# 7segDisplay.net
KiCad netlist of a schematic drawn in EAGLE
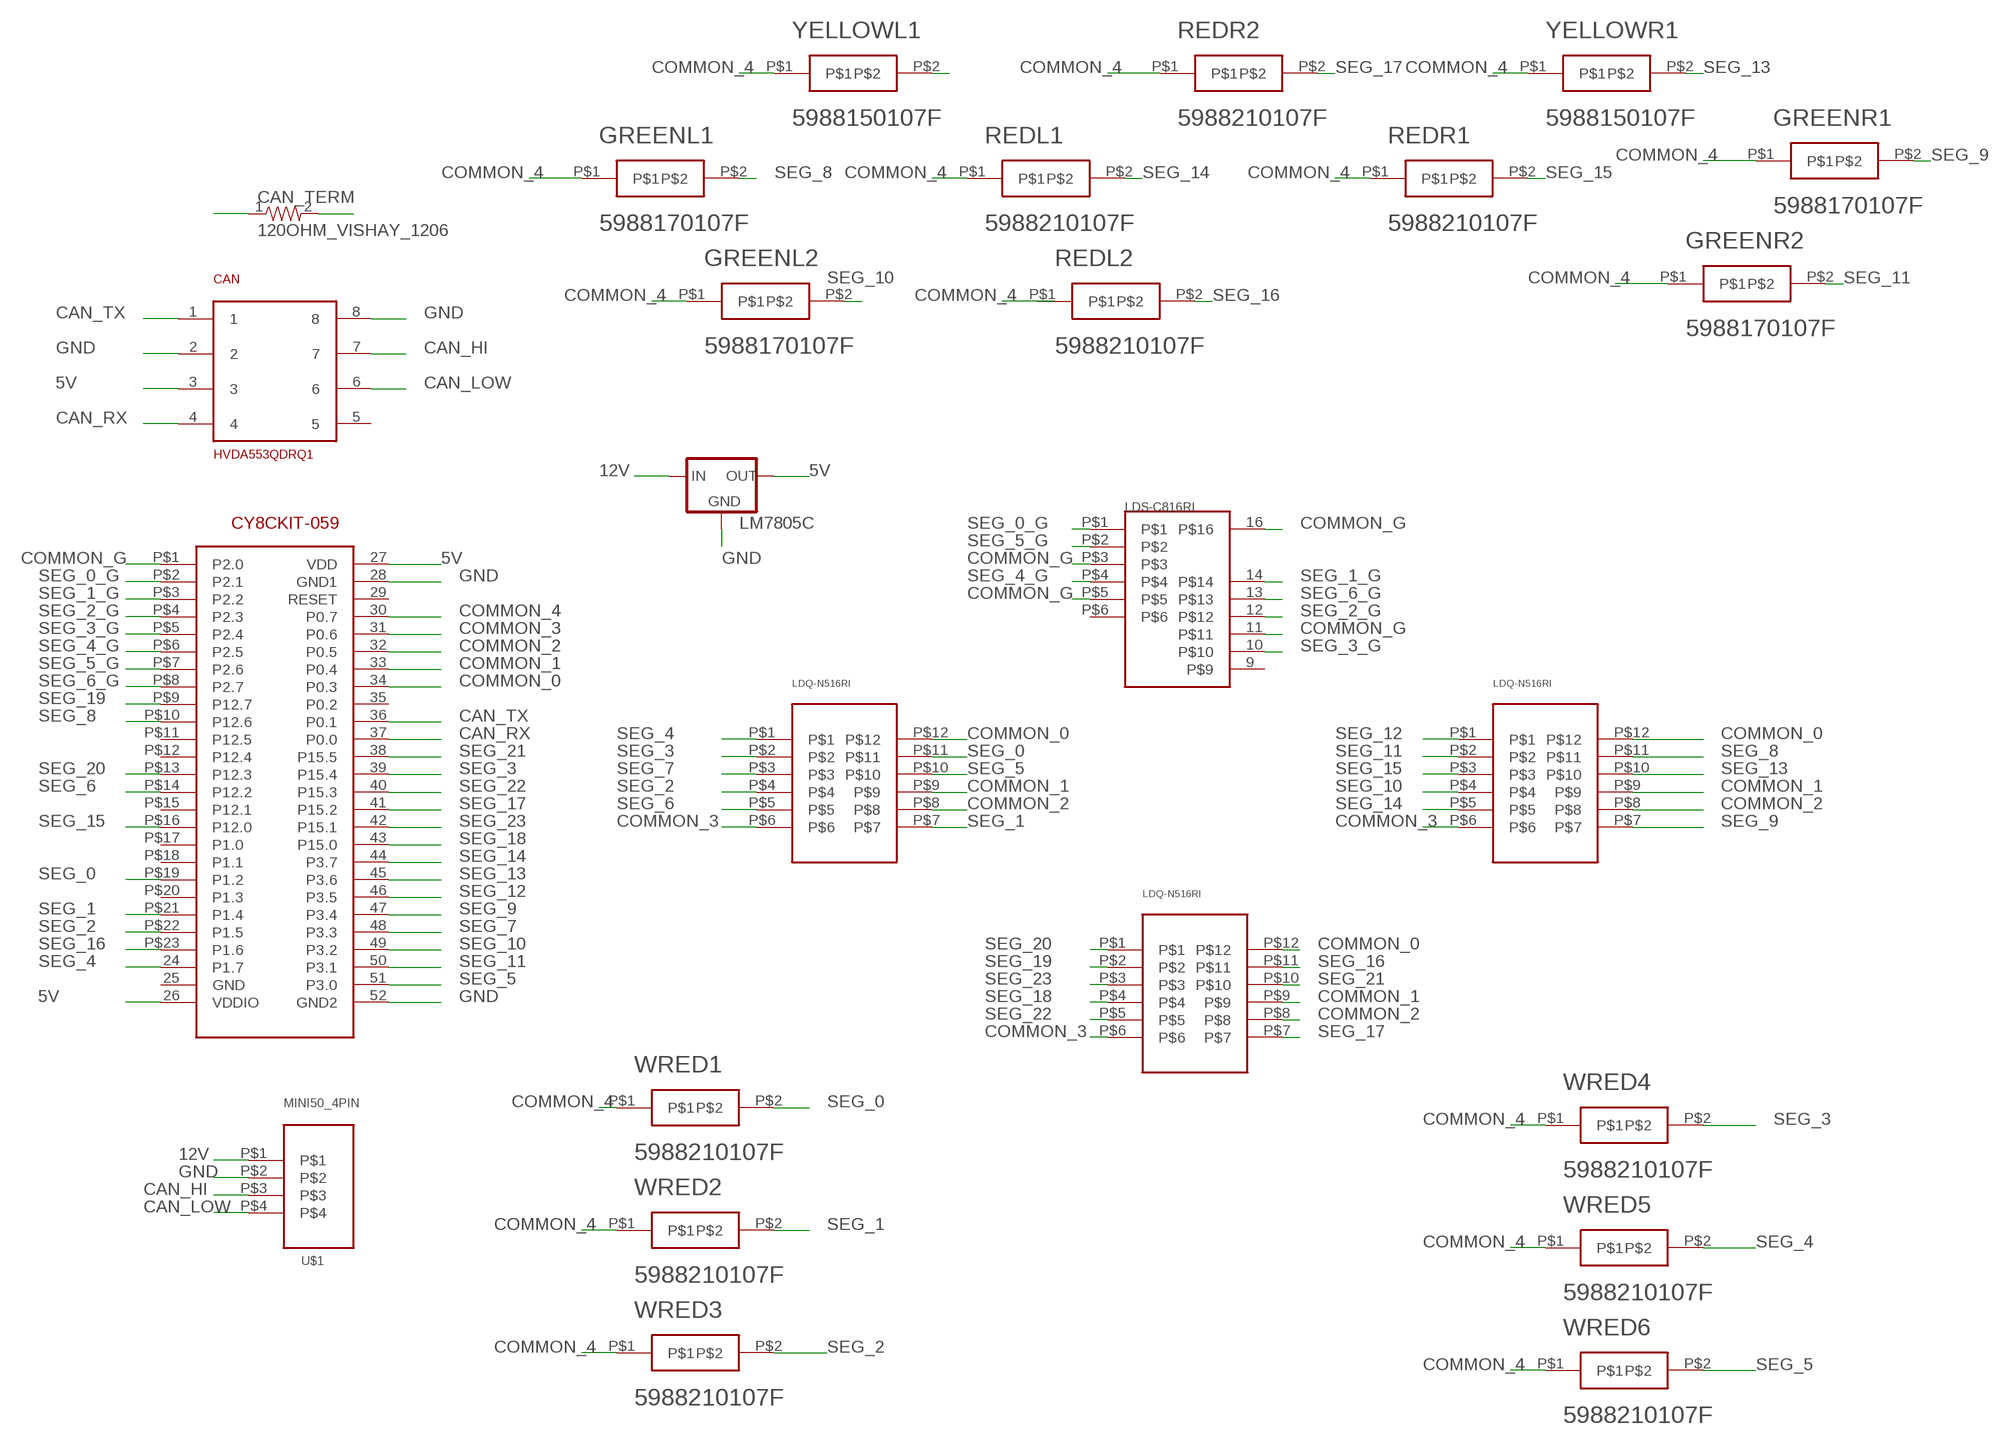
[diagram p0: schematic, sheet 1]

(export (version "E")
  (design (tool "Eeschema 10.0.6"))
  (components
    (comp (ref "BOTTOM")
      (value "LDQ-N516RI")
      (footprint "eagle-import:LDQ-N516RI")
      (libsource (lib "eagle-import") (part "LDQ-N516RI"))
    )
    (comp (ref "CAN")
      (value "HVDA553QDRQ1")
      (footprint "eagle-import:SOIC127P600X172-8N")
      (libsource (lib "eagle-import") (part "HVDA553QDRQ1"))
    )
    (comp (ref "CAN_TERM")
      (value "120OHM_VISHAY_1206")
      (footprint "eagle-import:1206")
      (libsource (lib "eagle-import") (part "120OHM_VISHAY_1206"))
    )
    (comp (ref "GEAR")
      (value "LDS-C816RITHROUGH_HOLE")
      (footprint "eagle-import:LDS-C816RI")
      (libsource (lib "eagle-import") (part "LDS-C816RITHROUGH_HOLE"))
    )
    (comp (ref "GREENL1")
      (value "5988170107F")
      (footprint "eagle-import:0805")
      (libsource (lib "eagle-import") (part "5988170107F"))
    )
    (comp (ref "GREENL2")
      (value "5988170107F")
      (footprint "eagle-import:0805")
      (libsource (lib "eagle-import") (part "5988170107F"))
    )
    (comp (ref "GREENR1")
      (value "5988170107F")
      (footprint "eagle-import:0805")
      (libsource (lib "eagle-import") (part "5988170107F"))
    )
    (comp (ref "GREENR2")
      (value "5988170107F")
      (footprint "eagle-import:0805")
      (libsource (lib "eagle-import") (part "5988170107F"))
    )
    (comp (ref "LEFT")
      (value "LDQ-N516RI")
      (footprint "eagle-import:LDQ-N516RI")
      (libsource (lib "eagle-import") (part "LDQ-N516RI"))
    )
    (comp (ref "LM7805C")
      (value "78XXL")
      (footprint "eagle-import:78XXL")
      (libsource (lib "eagle-import") (part "78XXL"))
    )
    (comp (ref "REDL1")
      (value "5988210107F")
      (footprint "eagle-import:1206")
      (libsource (lib "eagle-import") (part "5988210107F"))
    )
    (comp (ref "REDL2")
      (value "5988210107F")
      (footprint "eagle-import:1206")
      (libsource (lib "eagle-import") (part "5988210107F"))
    )
    (comp (ref "REDR1")
      (value "5988210107F")
      (footprint "eagle-import:1206")
      (libsource (lib "eagle-import") (part "5988210107F"))
    )
    (comp (ref "REDR2")
      (value "5988210107F")
      (footprint "eagle-import:1206")
      (libsource (lib "eagle-import") (part "5988210107F"))
    )
    (comp (ref "RIGHT")
      (value "LDQ-N516RI")
      (footprint "eagle-import:LDQ-N516RI")
      (libsource (lib "eagle-import") (part "LDQ-N516RI"))
    )
    (comp (ref "U$1")
      (value "MINI50_4PIN")
      (footprint "eagle-import:34792-0041")
      (libsource (lib "eagle-import") (part "MINI50_4PIN"))
    )
    (comp (ref "U$3")
      (value "CY8CKIT-059")
      (footprint "eagle-import:CY8CKIT-059")
      (libsource (lib "eagle-import") (part "CY8CKIT-059"))
    )
    (comp (ref "WRED1")
      (value "5988210107F")
      (footprint "eagle-import:1206")
      (libsource (lib "eagle-import") (part "5988210107F"))
    )
    (comp (ref "WRED2")
      (value "5988210107F")
      (footprint "eagle-import:1206")
      (libsource (lib "eagle-import") (part "5988210107F"))
    )
    (comp (ref "WRED3")
      (value "5988210107F")
      (footprint "eagle-import:1206")
      (libsource (lib "eagle-import") (part "5988210107F"))
    )
    (comp (ref "WRED4")
      (value "5988210107F")
      (footprint "eagle-import:1206")
      (libsource (lib "eagle-import") (part "5988210107F"))
    )
    (comp (ref "WRED5")
      (value "5988210107F")
      (footprint "eagle-import:1206")
      (libsource (lib "eagle-import") (part "5988210107F"))
    )
    (comp (ref "WRED6")
      (value "5988210107F")
      (footprint "eagle-import:1206")
      (libsource (lib "eagle-import") (part "5988210107F"))
    )
    (comp (ref "YELLOWL1")
      (value "5988150107F")
      (footprint "eagle-import:0805")
      (libsource (lib "eagle-import") (part "5988150107F"))
    )
    (comp (ref "YELLOWR1")
      (value "5988150107F")
      (footprint "eagle-import:0805")
      (libsource (lib "eagle-import") (part "5988150107F"))
    )
  )
  (nets
    (net (code "1") (name "/5V") (class "Default")
      (node (ref "CAN") (pin "3") (pinfunction "3_3") (pintype "bidirectional"))
      (node (ref "LM7805C") (pin "OUT") (pinfunction "OUT_OUT") (pintype "passive"))
      (node (ref "U$3") (pin "26") (pinfunction "VDDIO_26") (pintype "power_in"))
      (node (ref "U$3") (pin "27") (pinfunction "VDD_27") (pintype "power_in"))
    )
    (net (code "2") (name "/12V") (class "Default")
      (node (ref "LM7805C") (pin "IN") (pinfunction "IN_IN") (pintype "input"))
      (node (ref "U$1") (pin "P$1") (pinfunction "P$1_P$1") (pintype "bidirectional"))
    )
    (net (code "3") (name "/CAN_HI") (class "Default")
      (node (ref "CAN") (pin "7") (pinfunction "7_7") (pintype "bidirectional"))
      (node (ref "CAN_TERM") (pin "1") (pinfunction "1_1") (pintype "passive"))
      (node (ref "U$1") (pin "P$3") (pinfunction "P$3_P$3") (pintype "bidirectional"))
    )
    (net (code "4") (name "/CAN_LOW") (class "Default")
      (node (ref "CAN") (pin "6") (pinfunction "6_6") (pintype "bidirectional"))
      (node (ref "CAN_TERM") (pin "2") (pinfunction "2_2") (pintype "passive"))
      (node (ref "U$1") (pin "P$4") (pinfunction "P$4_P$4") (pintype "bidirectional"))
    )
    (net (code "5") (name "/CAN_RX") (class "Default")
      (node (ref "CAN") (pin "4") (pinfunction "4_4") (pintype "bidirectional"))
      (node (ref "U$3") (pin "37") (pinfunction "P0.0_37") (pintype "bidirectional"))
    )
    (net (code "6") (name "/CAN_TX") (class "Default")
      (node (ref "CAN") (pin "1") (pinfunction "1_1") (pintype "bidirectional"))
      (node (ref "U$3") (pin "36") (pinfunction "P0.1_36") (pintype "bidirectional"))
    )
    (net (code "7") (name "/COMMON_0") (class "Default")
      (node (ref "BOTTOM") (pin "P$12") (pinfunction "P$12_P$12") (pintype "bidirectional"))
      (node (ref "LEFT") (pin "P$12") (pinfunction "P$12_P$12") (pintype "bidirectional"))
      (node (ref "RIGHT") (pin "P$12") (pinfunction "P$12_P$12") (pintype "bidirectional"))
      (node (ref "U$3") (pin "34") (pinfunction "P0.3_34") (pintype "bidirectional"))
    )
    (net (code "8") (name "/COMMON_1") (class "Default")
      (node (ref "BOTTOM") (pin "P$9") (pinfunction "P$9_P$9") (pintype "bidirectional"))
      (node (ref "LEFT") (pin "P$9") (pinfunction "P$9_P$9") (pintype "bidirectional"))
      (node (ref "RIGHT") (pin "P$9") (pinfunction "P$9_P$9") (pintype "bidirectional"))
      (node (ref "U$3") (pin "33") (pinfunction "P0.4_33") (pintype "bidirectional"))
    )
    (net (code "9") (name "/COMMON_2") (class "Default")
      (node (ref "BOTTOM") (pin "P$8") (pinfunction "P$8_P$8") (pintype "bidirectional"))
      (node (ref "LEFT") (pin "P$8") (pinfunction "P$8_P$8") (pintype "bidirectional"))
      (node (ref "RIGHT") (pin "P$8") (pinfunction "P$8_P$8") (pintype "bidirectional"))
      (node (ref "U$3") (pin "32") (pinfunction "P0.5_32") (pintype "bidirectional"))
    )
    (net (code "10") (name "/COMMON_3") (class "Default")
      (node (ref "BOTTOM") (pin "P$6") (pinfunction "P$6_P$6") (pintype "bidirectional"))
      (node (ref "LEFT") (pin "P$6") (pinfunction "P$6_P$6") (pintype "bidirectional"))
      (node (ref "RIGHT") (pin "P$6") (pinfunction "P$6_P$6") (pintype "bidirectional"))
      (node (ref "U$3") (pin "31") (pinfunction "P0.6_31") (pintype "bidirectional"))
    )
    (net (code "11") (name "/COMMON_4") (class "Default")
      (node (ref "GREENL1") (pin "P$1") (pinfunction "P$1_P$1") (pintype "bidirectional"))
      (node (ref "GREENL2") (pin "P$1") (pinfunction "P$1_P$1") (pintype "bidirectional"))
      (node (ref "GREENR1") (pin "P$1") (pinfunction "P$1_P$1") (pintype "bidirectional"))
      (node (ref "GREENR2") (pin "P$1") (pinfunction "P$1_P$1") (pintype "bidirectional"))
      (node (ref "REDL1") (pin "P$1") (pinfunction "P$1_P$1") (pintype "bidirectional"))
      (node (ref "REDR1") (pin "P$1") (pinfunction "P$1_P$1") (pintype "bidirectional"))
      (node (ref "REDR2") (pin "P$1") (pinfunction "P$1_P$1") (pintype "bidirectional"))
      (node (ref "U$3") (pin "30") (pinfunction "P0.7_30") (pintype "bidirectional"))
      (node (ref "WRED1") (pin "P$1") (pinfunction "P$1_P$1") (pintype "bidirectional"))
      (node (ref "WRED2") (pin "P$1") (pinfunction "P$1_P$1") (pintype "bidirectional"))
      (node (ref "WRED3") (pin "P$1") (pinfunction "P$1_P$1") (pintype "bidirectional"))
      (node (ref "WRED4") (pin "P$1") (pinfunction "P$1_P$1") (pintype "bidirectional"))
      (node (ref "WRED5") (pin "P$1") (pinfunction "P$1_P$1") (pintype "bidirectional"))
      (node (ref "WRED6") (pin "P$1") (pinfunction "P$1_P$1") (pintype "bidirectional"))
      (node (ref "YELLOWL1") (pin "P$1") (pinfunction "P$1_P$1") (pintype "bidirectional"))
      (node (ref "YELLOWR1") (pin "P$1") (pinfunction "P$1_P$1") (pintype "bidirectional"))
    )
    (net (code "12") (name "/COMMON_G") (class "Default")
      (node (ref "GEAR") (pin "11") (pinfunction "P$11_11") (pintype "bidirectional"))
      (node (ref "GEAR") (pin "16") (pinfunction "P$16_16") (pintype "bidirectional"))
      (node (ref "GEAR") (pin "P$3") (pinfunction "P$3_P$3") (pintype "bidirectional"))
      (node (ref "GEAR") (pin "P$5") (pinfunction "P$5_P$5") (pintype "bidirectional"))
      (node (ref "U$3") (pin "P$1") (pinfunction "P2.0_P$1") (pintype "bidirectional"))
    )
    (net (code "13") (name "/GND") (class "Default")
      (node (ref "CAN") (pin "2") (pinfunction "2_2") (pintype "bidirectional"))
      (node (ref "CAN") (pin "8") (pinfunction "8_8") (pintype "bidirectional"))
      (node (ref "LM7805C") (pin "GND") (pinfunction "GND_GND") (pintype "input"))
      (node (ref "U$1") (pin "P$2") (pinfunction "P$2_P$2") (pintype "bidirectional"))
      (node (ref "U$3") (pin "28") (pinfunction "GND1_28") (pintype "bidirectional"))
      (node (ref "U$3") (pin "52") (pinfunction "GND2_52") (pintype "bidirectional"))
    )
    (net (code "14") (name "/SEG_0") (class "Default")
      (node (ref "LEFT") (pin "P$11") (pinfunction "P$11_P$11") (pintype "bidirectional"))
      (node (ref "U$3") (pin "P$19") (pinfunction "P1.2_P$19") (pintype "bidirectional"))
      (node (ref "WRED1") (pin "P$2") (pinfunction "P$2_P$2") (pintype "bidirectional"))
    )
    (net (code "15") (name "/SEG_0_G") (class "Default")
      (node (ref "GEAR") (pin "P$1") (pinfunction "P$1_P$1") (pintype "bidirectional"))
      (node (ref "U$3") (pin "P$2") (pinfunction "P2.1_P$2") (pintype "bidirectional"))
    )
    (net (code "16") (name "/SEG_1") (class "Default")
      (node (ref "LEFT") (pin "P$7") (pinfunction "P$7_P$7") (pintype "bidirectional"))
      (node (ref "U$3") (pin "P$21") (pinfunction "P1.4_P$21") (pintype "bidirectional"))
      (node (ref "WRED2") (pin "P$2") (pinfunction "P$2_P$2") (pintype "bidirectional"))
    )
    (net (code "17") (name "/SEG_1_G") (class "Default")
      (node (ref "GEAR") (pin "14") (pinfunction "P$14_14") (pintype "bidirectional"))
      (node (ref "U$3") (pin "P$3") (pinfunction "P2.2_P$3") (pintype "bidirectional"))
    )
    (net (code "18") (name "/SEG_2") (class "Default")
      (node (ref "LEFT") (pin "P$4") (pinfunction "P$4_P$4") (pintype "bidirectional"))
      (node (ref "U$3") (pin "P$22") (pinfunction "P1.5_P$22") (pintype "bidirectional"))
      (node (ref "WRED3") (pin "P$2") (pinfunction "P$2_P$2") (pintype "bidirectional"))
    )
    (net (code "19") (name "/SEG_2_G") (class "Default")
      (node (ref "GEAR") (pin "12") (pinfunction "P$12_12") (pintype "bidirectional"))
      (node (ref "U$3") (pin "P$4") (pinfunction "P2.3_P$4") (pintype "bidirectional"))
    )
    (net (code "20") (name "/SEG_3") (class "Default")
      (node (ref "LEFT") (pin "P$2") (pinfunction "P$2_P$2") (pintype "bidirectional"))
      (node (ref "U$3") (pin "39") (pinfunction "P15.4_39") (pintype "bidirectional"))
      (node (ref "WRED4") (pin "P$2") (pinfunction "P$2_P$2") (pintype "bidirectional"))
    )
    (net (code "21") (name "/SEG_3_G") (class "Default")
      (node (ref "GEAR") (pin "10") (pinfunction "P$10_10") (pintype "bidirectional"))
      (node (ref "U$3") (pin "P$5") (pinfunction "P2.4_P$5") (pintype "bidirectional"))
    )
    (net (code "22") (name "/SEG_4") (class "Default")
      (node (ref "LEFT") (pin "P$1") (pinfunction "P$1_P$1") (pintype "bidirectional"))
      (node (ref "U$3") (pin "24") (pinfunction "P1.7_24") (pintype "bidirectional"))
      (node (ref "WRED5") (pin "P$2") (pinfunction "P$2_P$2") (pintype "bidirectional"))
    )
    (net (code "23") (name "/SEG_4_G") (class "Default")
      (node (ref "GEAR") (pin "P$4") (pinfunction "P$4_P$4") (pintype "bidirectional"))
      (node (ref "U$3") (pin "P$6") (pinfunction "P2.5_P$6") (pintype "bidirectional"))
    )
    (net (code "24") (name "/SEG_5") (class "Default")
      (node (ref "LEFT") (pin "P$10") (pinfunction "P$10_P$10") (pintype "bidirectional"))
      (node (ref "U$3") (pin "51") (pinfunction "P3.0_51") (pintype "bidirectional"))
      (node (ref "WRED6") (pin "P$2") (pinfunction "P$2_P$2") (pintype "bidirectional"))
    )
    (net (code "25") (name "/SEG_5_G") (class "Default")
      (node (ref "GEAR") (pin "P$2") (pinfunction "P$2_P$2") (pintype "bidirectional"))
      (node (ref "U$3") (pin "P$7") (pinfunction "P2.6_P$7") (pintype "bidirectional"))
    )
    (net (code "26") (name "/SEG_6") (class "Default")
      (node (ref "LEFT") (pin "P$5") (pinfunction "P$5_P$5") (pintype "bidirectional"))
      (node (ref "U$3") (pin "P$14") (pinfunction "P12.2_P$14") (pintype "bidirectional"))
    )
    (net (code "27") (name "/SEG_6_G") (class "Default")
      (node (ref "GEAR") (pin "13") (pinfunction "P$13_13") (pintype "bidirectional"))
      (node (ref "U$3") (pin "P$8") (pinfunction "P2.7_P$8") (pintype "bidirectional"))
    )
    (net (code "28") (name "/SEG_7") (class "Default")
      (node (ref "LEFT") (pin "P$3") (pinfunction "P$3_P$3") (pintype "bidirectional"))
      (node (ref "U$3") (pin "48") (pinfunction "P3.3_48") (pintype "bidirectional"))
    )
    (net (code "29") (name "/SEG_8") (class "Default")
      (node (ref "GREENL1") (pin "P$2") (pinfunction "P$2_P$2") (pintype "bidirectional"))
      (node (ref "RIGHT") (pin "P$11") (pinfunction "P$11_P$11") (pintype "bidirectional"))
      (node (ref "U$3") (pin "P$10") (pinfunction "P12.6_P$10") (pintype "bidirectional"))
    )
    (net (code "30") (name "/SEG_9") (class "Default")
      (node (ref "GREENR1") (pin "P$2") (pinfunction "P$2_P$2") (pintype "bidirectional"))
      (node (ref "RIGHT") (pin "P$7") (pinfunction "P$7_P$7") (pintype "bidirectional"))
      (node (ref "U$3") (pin "47") (pinfunction "P3.4_47") (pintype "bidirectional"))
    )
    (net (code "31") (name "/SEG_10") (class "Default")
      (node (ref "GREENL2") (pin "P$2") (pinfunction "P$2_P$2") (pintype "bidirectional"))
      (node (ref "RIGHT") (pin "P$4") (pinfunction "P$4_P$4") (pintype "bidirectional"))
      (node (ref "U$3") (pin "49") (pinfunction "P3.2_49") (pintype "bidirectional"))
    )
    (net (code "32") (name "/SEG_11") (class "Default")
      (node (ref "GREENR2") (pin "P$2") (pinfunction "P$2_P$2") (pintype "bidirectional"))
      (node (ref "RIGHT") (pin "P$2") (pinfunction "P$2_P$2") (pintype "bidirectional"))
      (node (ref "U$3") (pin "50") (pinfunction "P3.1_50") (pintype "bidirectional"))
    )
    (net (code "33") (name "/SEG_12") (class "Default")
      (node (ref "RIGHT") (pin "P$1") (pinfunction "P$1_P$1") (pintype "bidirectional"))
      (node (ref "U$3") (pin "46") (pinfunction "P3.5_46") (pintype "bidirectional"))
      (node (ref "YELLOWL1") (pin "P$2") (pinfunction "P$2_P$2") (pintype "bidirectional"))
    )
    (net (code "34") (name "/SEG_13") (class "Default")
      (node (ref "RIGHT") (pin "P$10") (pinfunction "P$10_P$10") (pintype "bidirectional"))
      (node (ref "U$3") (pin "45") (pinfunction "P3.6_45") (pintype "bidirectional"))
      (node (ref "YELLOWR1") (pin "P$2") (pinfunction "P$2_P$2") (pintype "bidirectional"))
    )
    (net (code "35") (name "/SEG_14") (class "Default")
      (node (ref "REDL1") (pin "P$2") (pinfunction "P$2_P$2") (pintype "bidirectional"))
      (node (ref "RIGHT") (pin "P$5") (pinfunction "P$5_P$5") (pintype "bidirectional"))
      (node (ref "U$3") (pin "44") (pinfunction "P3.7_44") (pintype "bidirectional"))
    )
    (net (code "36") (name "/SEG_15") (class "Default")
      (node (ref "REDR1") (pin "P$2") (pinfunction "P$2_P$2") (pintype "bidirectional"))
      (node (ref "RIGHT") (pin "P$3") (pinfunction "P$3_P$3") (pintype "bidirectional"))
      (node (ref "U$3") (pin "P$16") (pinfunction "P12.0_P$16") (pintype "bidirectional"))
    )
    (net (code "37") (name "/SEG_16") (class "Default")
      (node (ref "BOTTOM") (pin "P$11") (pinfunction "P$11_P$11") (pintype "bidirectional"))
      (node (ref "REDL2") (pin "P$2") (pinfunction "P$2_P$2") (pintype "bidirectional"))
      (node (ref "U$3") (pin "P$23") (pinfunction "P1.6_P$23") (pintype "bidirectional"))
    )
    (net (code "38") (name "/SEG_17") (class "Default")
      (node (ref "BOTTOM") (pin "P$7") (pinfunction "P$7_P$7") (pintype "bidirectional"))
      (node (ref "REDR2") (pin "P$2") (pinfunction "P$2_P$2") (pintype "bidirectional"))
      (node (ref "U$3") (pin "41") (pinfunction "P15.2_41") (pintype "bidirectional"))
    )
    (net (code "39") (name "/SEG_18") (class "Default")
      (node (ref "BOTTOM") (pin "P$4") (pinfunction "P$4_P$4") (pintype "bidirectional"))
      (node (ref "U$3") (pin "43") (pinfunction "P15.0_43") (pintype "bidirectional"))
    )
    (net (code "40") (name "/SEG_19") (class "Default")
      (node (ref "BOTTOM") (pin "P$2") (pinfunction "P$2_P$2") (pintype "bidirectional"))
      (node (ref "U$3") (pin "P$9") (pinfunction "P12.7_P$9") (pintype "bidirectional"))
    )
    (net (code "41") (name "/SEG_20") (class "Default")
      (node (ref "BOTTOM") (pin "P$1") (pinfunction "P$1_P$1") (pintype "bidirectional"))
      (node (ref "U$3") (pin "P$13") (pinfunction "P12.3_P$13") (pintype "bidirectional"))
    )
    (net (code "42") (name "/SEG_21") (class "Default")
      (node (ref "BOTTOM") (pin "P$10") (pinfunction "P$10_P$10") (pintype "bidirectional"))
      (node (ref "U$3") (pin "38") (pinfunction "P15.5_38") (pintype "bidirectional"))
    )
    (net (code "43") (name "/SEG_22") (class "Default")
      (node (ref "BOTTOM") (pin "P$5") (pinfunction "P$5_P$5") (pintype "bidirectional"))
      (node (ref "U$3") (pin "40") (pinfunction "P15.3_40") (pintype "bidirectional"))
    )
    (net (code "44") (name "/SEG_23") (class "Default")
      (node (ref "BOTTOM") (pin "P$3") (pinfunction "P$3_P$3") (pintype "bidirectional"))
      (node (ref "U$3") (pin "42") (pinfunction "P15.1_42") (pintype "bidirectional"))
    )
    (net (code "45") (name "unconnected-(CAN-Pad5)") (class "Default")
      (node (ref "CAN") (pin "5") (pinfunction "5_5") (pintype "bidirectional"))
    )
    (net (code "46") (name "unconnected-(GEAR-P$9-Pad9)") (class "Default")
      (node (ref "GEAR") (pin "9") (pinfunction "P$9_9") (pintype "bidirectional"))
    )
    (net (code "47") (name "unconnected-(GEAR-PadP$6)") (class "Default")
      (node (ref "GEAR") (pin "P$6") (pinfunction "P$6_P$6") (pintype "bidirectional"))
    )
    (net (code "48") (name "unconnected-(REDL2-PadP$1)") (class "Default")
      (node (ref "REDL2") (pin "P$1") (pinfunction "P$1_P$1") (pintype "bidirectional"))
    )
    (net (code "49") (name "unconnected-(U$3-GND-Pad25)") (class "Default")
      (node (ref "U$3") (pin "25") (pinfunction "GND_25") (pintype "bidirectional"))
    )
    (net (code "50") (name "unconnected-(U$3-P0.2-Pad35)") (class "Default")
      (node (ref "U$3") (pin "35") (pinfunction "P0.2_35") (pintype "bidirectional"))
    )
    (net (code "51") (name "unconnected-(U$3-P1.0-PadP$17)") (class "Default")
      (node (ref "U$3") (pin "P$17") (pinfunction "P1.0_P$17") (pintype "bidirectional"))
    )
    (net (code "52") (name "unconnected-(U$3-P1.1-PadP$18)") (class "Default")
      (node (ref "U$3") (pin "P$18") (pinfunction "P1.1_P$18") (pintype "bidirectional"))
    )
    (net (code "53") (name "unconnected-(U$3-P1.3-PadP$20)") (class "Default")
      (node (ref "U$3") (pin "P$20") (pinfunction "P1.3_P$20") (pintype "bidirectional"))
    )
    (net (code "54") (name "unconnected-(U$3-P12.1-PadP$15)") (class "Default")
      (node (ref "U$3") (pin "P$15") (pinfunction "P12.1_P$15") (pintype "bidirectional"))
    )
    (net (code "55") (name "unconnected-(U$3-P12.4-PadP$12)") (class "Default")
      (node (ref "U$3") (pin "P$12") (pinfunction "P12.4_P$12") (pintype "bidirectional"))
    )
    (net (code "56") (name "unconnected-(U$3-P12.5-PadP$11)") (class "Default")
      (node (ref "U$3") (pin "P$11") (pinfunction "P12.5_P$11") (pintype "bidirectional"))
    )
    (net (code "57") (name "unconnected-(U$3-RESET-Pad29)") (class "Default")
      (node (ref "U$3") (pin "29") (pinfunction "RESET_29") (pintype "bidirectional"))
    )
  )
)
